# Top.net
KiCad netlist of a schematic drawn in Altium Designer
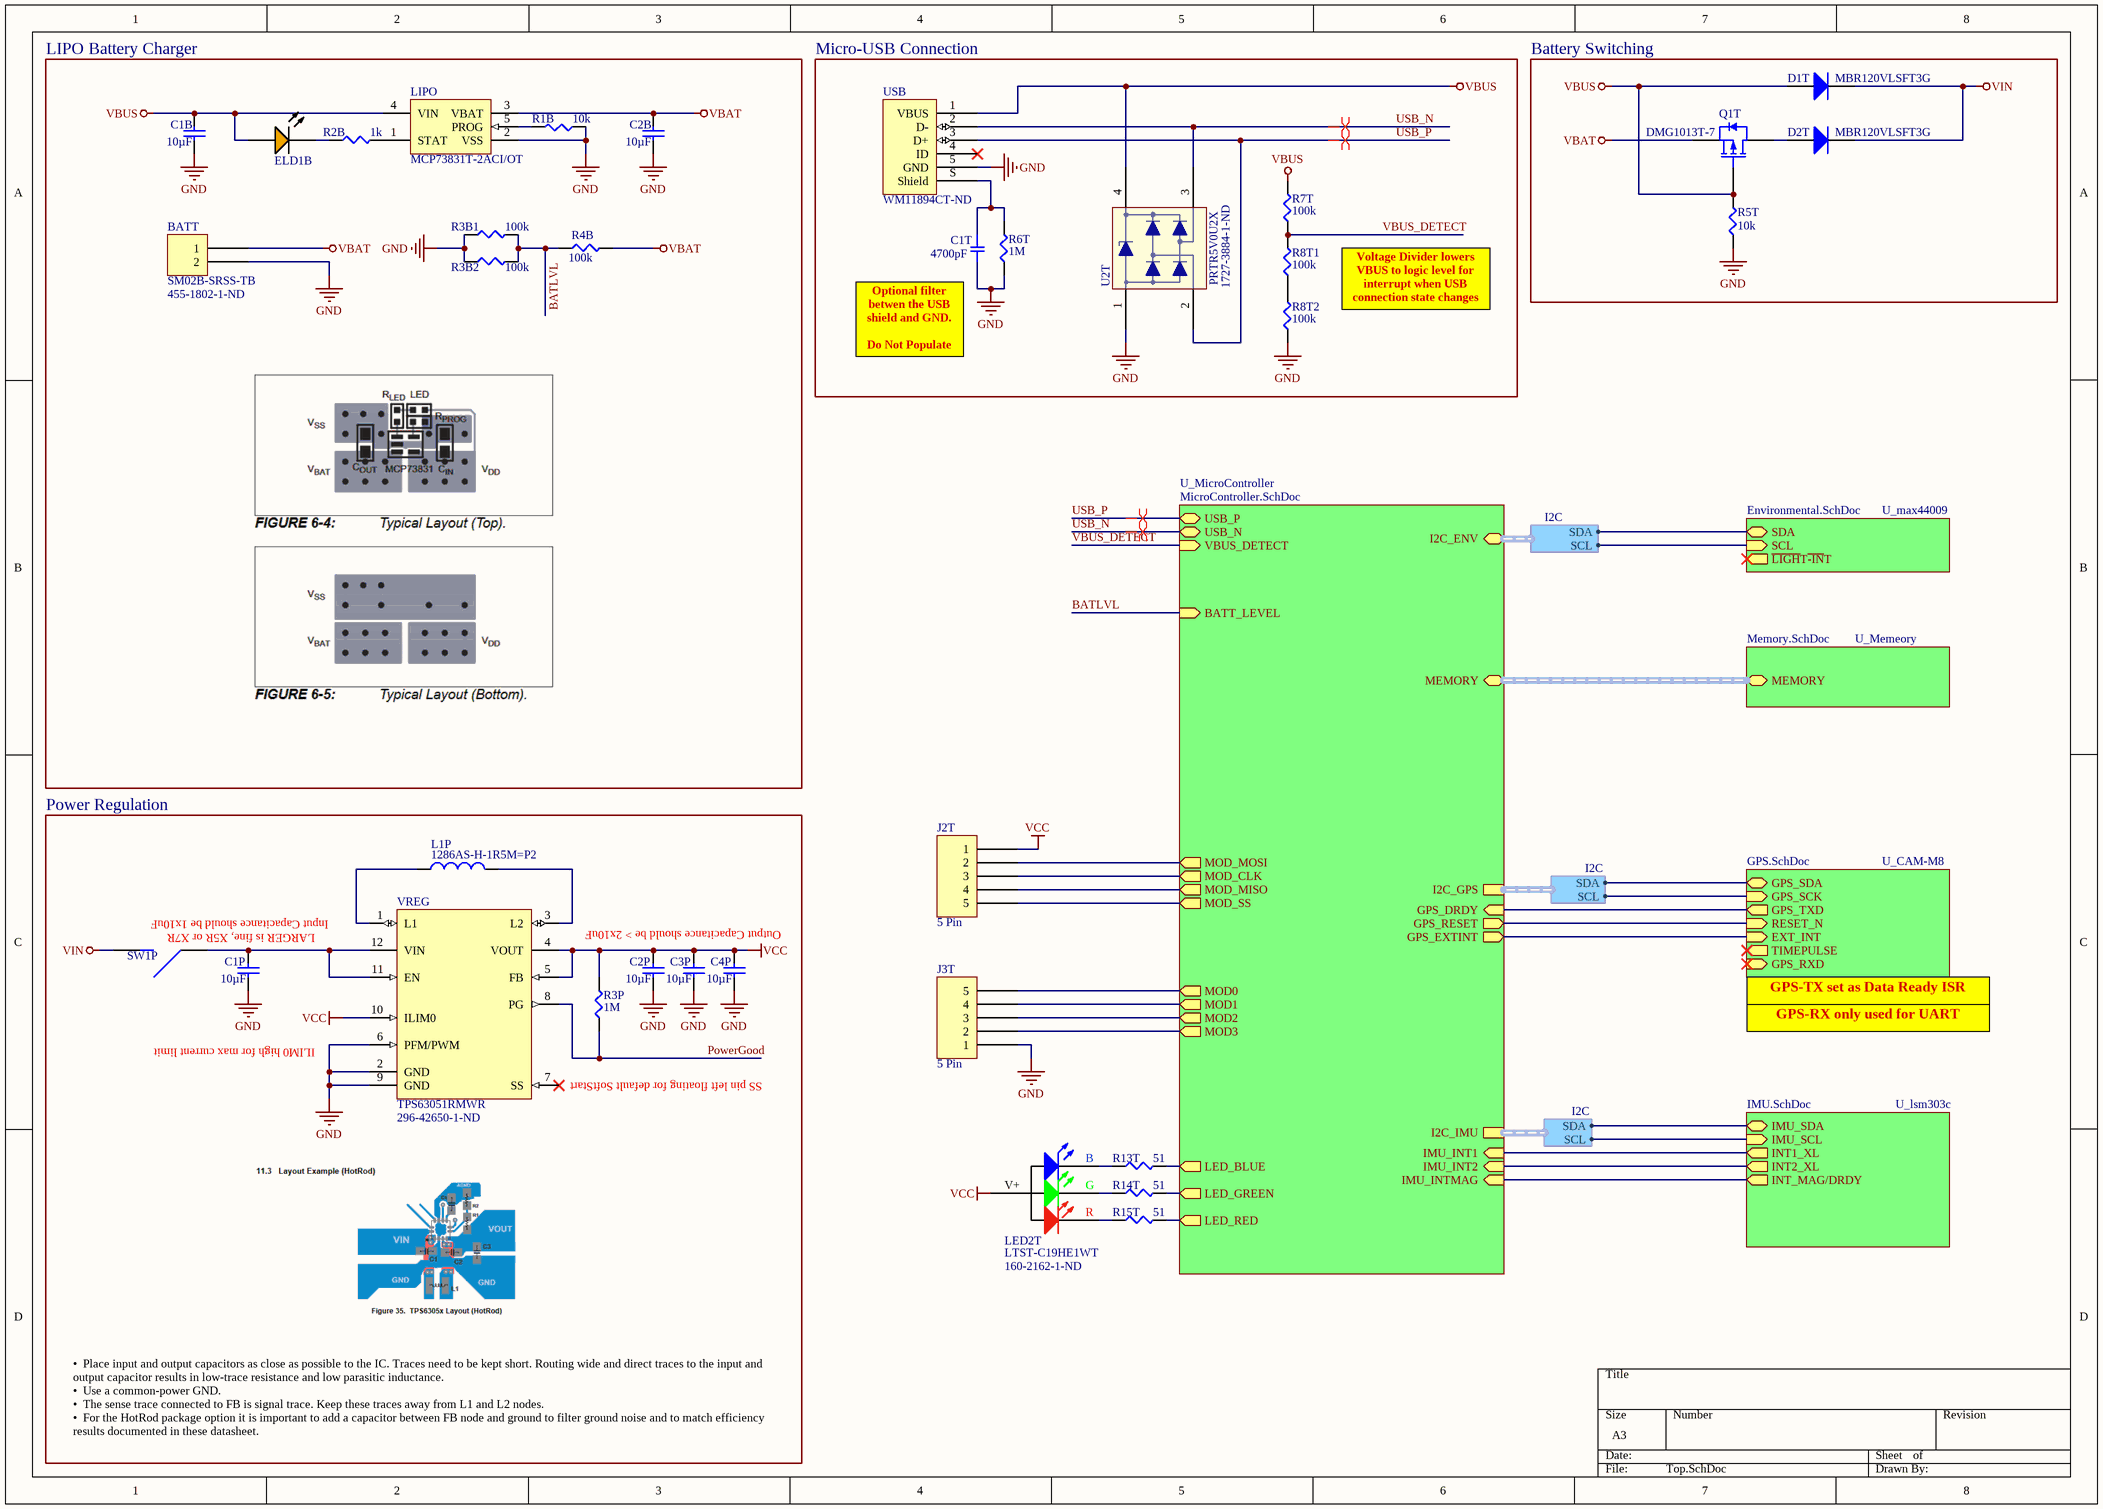
[diagram p0: Top.SchDoc]

(export (version "E")
  (design (tool "Eeschema 10.0.6"))
  (components
    (comp (ref "BATT")
      (value "SM02B-SRSS-TB")
      (footprint "JST S2B-PH-SM4")
      (fields (field (name "SUPPLIER PART NUMBER 1") "455-1802-1-ND"))
      (libsource (lib "Connectors") (part "2 Pin"))
    )
    (comp (ref "C1B")
      (value "GRT188R61C106KE13D")
      (footprint "C0603N")
      (description "10µF 16V Ceramic Capacitor X5R 0603")
      (fields
        (field (name "HOUSEPART") "NO")
        (field (name "TOLERANCE") "±10%")
        (field (name "CAPACITANCE") "10µF")
      )
      (libsource (lib "MF_Passives") (part "CAPACITOR_NP"))
    )
    (comp (ref "C1P")
      (value "GRT188R61C106KE13D")
      (footprint "C0603N")
      (description "10µF 16V Ceramic Capacitor X5R 0603")
      (fields
        (field (name "HOUSEPART") "NO")
        (field (name "TOLERANCE") "±10%")
        (field (name "CAPACITANCE") "10µF")
      )
      (libsource (lib "MF_Passives") (part "CAPACITOR_NP"))
    )
    (comp (ref "C1T")
      (value "4700pF")
      (footprint "C0603N")
      (description "CAP CER 4700PF 100V X7R 0603")
      (fields
        (field (name "DIGI-KEY PART NUMBER") "490-4930-1-ND")
        (field (name "PART NUMBER") "GCM188R72A472KA37D")
      )
      (libsource (lib "capacitor_murata_0603") (part "GCM188R72A472KA37D"))
    )
    (comp (ref "C2B")
      (value "GRT188R61C106KE13D")
      (footprint "C0603N")
      (description "10µF 16V Ceramic Capacitor X5R 0603")
      (fields
        (field (name "HOUSEPART") "NO")
        (field (name "TOLERANCE") "±10%")
        (field (name "CAPACITANCE") "10µF")
      )
      (libsource (lib "MF_Passives") (part "CAPACITOR_NP"))
    )
    (comp (ref "C2P")
      (value "GRT188R61C106KE13D")
      (footprint "C0603N")
      (description "10µF 16V Ceramic Capacitor X5R 0603")
      (fields
        (field (name "HOUSEPART") "NO")
        (field (name "TOLERANCE") "±10%")
        (field (name "CAPACITANCE") "10µF")
      )
      (libsource (lib "MF_Passives") (part "CAPACITOR_NP"))
    )
    (comp (ref "C3P")
      (value "GRT188R61C106KE13D")
      (footprint "C0603N")
      (description "10µF 16V Ceramic Capacitor X5R 0603")
      (fields
        (field (name "HOUSEPART") "NO")
        (field (name "TOLERANCE") "±10%")
        (field (name "CAPACITANCE") "10µF")
      )
      (libsource (lib "MF_Passives") (part "CAPACITOR_NP"))
    )
    (comp (ref "C4P")
      (value "GRT188R61C106KE13D")
      (footprint "C0603N")
      (description "10µF 16V Ceramic Capacitor X5R 0603")
      (fields
        (field (name "HOUSEPART") "NO")
        (field (name "TOLERANCE") "±10%")
        (field (name "CAPACITANCE") "10µF")
      )
      (libsource (lib "MF_Passives") (part "CAPACITOR_NP"))
    )
    (comp (ref "D1T")
      (value "MBR120VLSFT3G")
      (footprint "MBR120VLSFT3G")
      (description "Diode Schottky 20V 1A Surface Mount SOD-123FL")
      (libsource (lib "OnSemi") (part "MBR120VLSFT3G"))
    )
    (comp (ref "D2T")
      (value "MBR120VLSFT3G")
      (footprint "MBR120VLSFT3G")
      (description "Diode Schottky 20V 1A Surface Mount SOD-123FL")
      (libsource (lib "OnSemi") (part "MBR120VLSFT3G"))
    )
    (comp (ref "ELD1B")
      (value "LTST-C190KFKT")
      (footprint "LED_0603")
      (description "LED Uni-Color Orange, 75 mW, 30 mA")
      (libsource (lib "Lite-On") (part "CMP-1544850-3"))
    )
    (comp (ref "J2T") (value "5 Pin") (footprint "Pinhead_1x5") (libsource (lib "") (part "5 Pin_1")))
    (comp (ref "J3T") (value "5 Pin") (footprint "Pinhead_1x5") (libsource (lib "Connectors") (part "5 Pin")))
    (comp (ref "L1P")
      (value "1286AS-H-1R5M=P2")
      (footprint "L0806_N")
      (description "FIXED IND 1.5UH 2A 114 MOHM SMD")
      (libsource (lib "Passives") (part "INDUCTOR"))
    )
    (comp (ref "LED2T")
      (value "LTST-C19HE1WT")
      (footprint "LED_0606_160X160X35")
      (description "RGB LED 0606 (1616 metric)")
      (fields (field (name "SUPPLIER PART NUMBER 1") "160-2162-1-ND"))
      (libsource (lib "Lite-On") (part "LTST-C19HE1WT"))
    )
    (comp (ref "LIPO")
      (value "MCP73831T-2ACI/OT")
      (footprint "SOT-23-5_MC")
      (description "MCP73831 Series Single-Cell Li-Ion/Li-Polymer Battery Charge Controller SOT-23-5")
      (libsource (lib "Microchip") (part "MCHP-MCP73831T-5"))
    )
    (comp (ref "Q1T")
      (value "DMG1013T-7")
      (footprint "SOT50P175X90-3N")
      (description "P-Channel SOT-523")
      (libsource (lib "diodesInc") (part "DMG1013T-7c2930a883c7b1d54"))
    )
    (comp (ref "R1B")
      (value "10k")
      (footprint "SMD-0603-RES")
      (description "RES SMD 10K OHM 1% 1/10W 0603")
      (fields
        (field (name "PART NUMBER") "ERJ-3EKF1002V")
        (field (name "DIGI-KEY PART NUMBER") "P10.0KHCT-ND")
      )
      (libsource (lib "Panasonic_ERJ_0603") (part "ERJ-3EKF1002V"))
    )
    (comp (ref "R2B")
      (value "1k")
      (footprint "SMD-0603-RES")
      (description "RES SMD 1K OHM 1% 1/10W 0603")
      (fields
        (field (name "PART NUMBER") "ERJ-3EKF1001V")
        (field (name "DIGI-KEY PART NUMBER") "P1.00KHCT-ND")
      )
      (libsource (lib "Panasonic_ERJ_0603") (part "ERJ-3EKF1001V"))
    )
    (comp (ref "R3B1")
      (value "100k")
      (footprint "SMD-0603-RES")
      (description "RES SMD 100K OHM 1% 1/10W 0603")
      (fields
        (field (name "PART NUMBER") "ERJ-3EKF1003V")
        (field (name "DIGI-KEY PART NUMBER") "P100KHCT-ND")
      )
      (libsource (lib "Panasonic_ERJ_0603") (part "ERJ-3EKF1003V"))
    )
    (comp (ref "R3B2")
      (value "100k")
      (footprint "SMD-0603-RES")
      (description "RES SMD 100K OHM 1% 1/10W 0603")
      (fields
        (field (name "PART NUMBER") "ERJ-3EKF1003V")
        (field (name "DIGI-KEY PART NUMBER") "P100KHCT-ND")
      )
      (libsource (lib "Panasonic_ERJ_0603") (part "ERJ-3EKF1003V"))
    )
    (comp (ref "R3P")
      (value "1M")
      (footprint "SMD-0603-RES")
      (description "RES SMD 1M OHM 1% 1/10W 0603")
      (fields
        (field (name "PART NUMBER") "ERJ-3EKF1004V")
        (field (name "DIGI-KEY PART NUMBER") "P1.00MHCT-ND")
      )
      (libsource (lib "Panasonic_ERJ_0603") (part "ERJ-3EKF1004V"))
    )
    (comp (ref "R4B")
      (value "100k")
      (footprint "SMD-0603-RES")
      (description "RES SMD 100K OHM 1% 1/10W 0603")
      (fields
        (field (name "PART NUMBER") "ERJ-3EKF1003V")
        (field (name "DIGI-KEY PART NUMBER") "P100KHCT-ND")
      )
      (libsource (lib "Panasonic_ERJ_0603") (part "ERJ-3EKF1003V"))
    )
    (comp (ref "R5T")
      (value "10k")
      (footprint "SMD-0603-RES")
      (description "RES SMD 10K OHM 1% 1/10W 0603")
      (fields
        (field (name "PART NUMBER") "ERJ-3EKF1002V")
        (field (name "DIGI-KEY PART NUMBER") "P10.0KHCT-ND")
      )
      (libsource (lib "Panasonic_ERJ_0603") (part "ERJ-3EKF1002V"))
    )
    (comp (ref "R6T")
      (value "1M")
      (footprint "SMD-0603-RES")
      (description "RES SMD 1M OHM 1% 1/10W 0603")
      (fields
        (field (name "PART NUMBER") "ERJ-3EKF1004V")
        (field (name "DIGI-KEY PART NUMBER") "P1.00MHCT-ND")
      )
      (libsource (lib "Panasonic_ERJ_0603") (part "ERJ-3EKF1004V"))
    )
    (comp (ref "R7T")
      (value "100k")
      (footprint "SMD-0603-RES")
      (description "RES SMD 100K OHM 1% 1/10W 0603")
      (fields
        (field (name "PART NUMBER") "ERJ-3EKF1003V")
        (field (name "DIGI-KEY PART NUMBER") "P100KHCT-ND")
      )
      (libsource (lib "Panasonic_ERJ_0603") (part "ERJ-3EKF1003V"))
    )
    (comp (ref "R8T1")
      (value "100k")
      (footprint "SMD-0603-RES")
      (description "RES SMD 100K OHM 1% 1/10W 0603")
      (fields
        (field (name "PART NUMBER") "ERJ-3EKF1003V")
        (field (name "DIGI-KEY PART NUMBER") "P100KHCT-ND")
      )
      (libsource (lib "Panasonic_ERJ_0603") (part "ERJ-3EKF1003V"))
    )
    (comp (ref "R8T2")
      (value "100k")
      (footprint "SMD-0603-RES")
      (description "RES SMD 100K OHM 1% 1/10W 0603")
      (fields
        (field (name "PART NUMBER") "ERJ-3EKF1003V")
        (field (name "DIGI-KEY PART NUMBER") "P100KHCT-ND")
      )
      (libsource (lib "Panasonic_ERJ_0603") (part "ERJ-3EKF1003V"))
    )
    (comp (ref "R13T")
      (value "51")
      (footprint "SMD-0603-RES")
      (description "RES SMD 51 OHM 1% 1/10W 0603")
      (fields
        (field (name "PART NUMBER") "ERJ-3EKF51R0V")
        (field (name "DIGI-KEY PART NUMBER") "P51.0HCT-ND")
      )
      (libsource (lib "Panasonic_ERJ_0603") (part "ERJ-3EKF51R0V"))
    )
    (comp (ref "R14T")
      (value "51")
      (footprint "SMD-0603-RES")
      (description "RES SMD 51 OHM 1% 1/10W 0603")
      (fields
        (field (name "PART NUMBER") "ERJ-3EKF51R0V")
        (field (name "DIGI-KEY PART NUMBER") "P51.0HCT-ND")
      )
      (libsource (lib "Panasonic_ERJ_0603") (part "ERJ-3EKF51R0V"))
    )
    (comp (ref "R15T")
      (value "51")
      (footprint "SMD-0603-RES")
      (description "RES SMD 51 OHM 1% 1/10W 0603")
      (fields
        (field (name "PART NUMBER") "ERJ-3EKF51R0V")
        (field (name "DIGI-KEY PART NUMBER") "P51.0HCT-ND")
      )
      (libsource (lib "Panasonic_ERJ_0603") (part "ERJ-3EKF51R0V"))
    )
    (comp (ref "SW1P")
      (value "SPST")
      (footprint "Pinhead254_90_1x2")
      (description "SPST Switch")
      (libsource (lib "mechanical") (part "SPST switch"))
    )
    (comp (ref "U2T")
      (value "PRTR5V0U2X")
      (footprint "SOT143B")
      (fields (field (name "SUPPLIER PART NUMBER 1") "1727-3884-1-ND"))
      (libsource (lib "PRTR5V0U2X") (part "PRTR5V0U2X"))
    )
    (comp (ref "USB")
      (value "WM11894CT-ND")
      (footprint "MOLEX_105443-1101")
      (libsource (lib "Connectors") (part "USB 2.0 Type B Micro"))
    )
    (comp (ref "VREG")
      (value "TPS63051RMWR")
      (footprint "QFN12P50_250X250X100")
      (description "Single Inductor Buck Boost Converter 12-VQFN")
      (fields
        (field (name "MANUFACTURER") "Texas Instruments")
        (field (name "SUPPLIER PART NUMBER 1") "296-42650-1-ND")
      )
      (libsource (lib "TI") (part "TPS63051RMWR"))
    )
  )
  (nets
    (net (code "2") (name "/BATLVL") (class "Default")
      (node (ref "R3B1") (pin "2") (pinfunction "2_2") (pintype "passive"))
      (node (ref "R3B2") (pin "2") (pinfunction "2_2") (pintype "passive"))
      (node (ref "R4B") (pin "1") (pinfunction "1_1") (pintype "passive"))
    )
    (net (code "14") (name "/LED_BLUE") (class "Default")
      (node (ref "R13T") (pin "2") (pinfunction "2_2") (pintype "passive"))
    )
    (net (code "15") (name "/LED_GREEN") (class "Default")
      (node (ref "R14T") (pin "2") (pinfunction "2_2") (pintype "passive"))
    )
    (net (code "16") (name "/LED_RED") (class "Default")
      (node (ref "R15T") (pin "2") (pinfunction "2_2") (pintype "passive"))
    )
    (net (code "18") (name "/MOD0") (class "Default")
      (node (ref "J3T") (pin "5") (pinfunction "5_5") (pintype "passive"))
    )
    (net (code "19") (name "/MOD1") (class "Default")
      (node (ref "J3T") (pin "4") (pinfunction "4_4") (pintype "passive"))
    )
    (net (code "20") (name "/MOD2") (class "Default")
      (node (ref "J3T") (pin "3") (pinfunction "3_3") (pintype "passive"))
    )
    (net (code "21") (name "/MOD3") (class "Default")
      (node (ref "J3T") (pin "2") (pinfunction "2_2") (pintype "passive"))
    )
    (net (code "22") (name "/MOD_CLK") (class "Default")
      (node (ref "J2T") (pin "3") (pinfunction "3_3") (pintype "passive"))
    )
    (net (code "23") (name "/MOD_MISO") (class "Default")
      (node (ref "J2T") (pin "4") (pinfunction "4_4") (pintype "passive"))
    )
    (net (code "24") (name "/MOD_MOSI") (class "Default")
      (node (ref "J2T") (pin "2") (pinfunction "2_2") (pintype "passive"))
    )
    (net (code "25") (name "/MOD_SS") (class "Default")
      (node (ref "J2T") (pin "5") (pinfunction "5_5") (pintype "passive"))
    )
    (net (code "26") (name "/PowerGood") (class "Default")
      (node (ref "R3P") (pin "1") (pinfunction "1_1") (pintype "passive"))
      (node (ref "VREG") (pin "8") (pinfunction "PG_8") (pintype "output"))
    )
    (net (code "30") (name "/USB_N") (class "Default")
      (node (ref "U2T") (pin "3") (pinfunction "I/O2_3") (pintype "passive"))
      (node (ref "USB") (pin "2") (pinfunction "D-_2") (pintype "bidirectional"))
    )
    (net (code "31") (name "/USB_P") (class "Default")
      (node (ref "U2T") (pin "2") (pinfunction "I/O1_2") (pintype "passive"))
      (node (ref "USB") (pin "3") (pinfunction "D+_3") (pintype "bidirectional"))
    )
    (net (code "32") (name "/VBUS_DETECT") (class "Default")
      (node (ref "R7T") (pin "1") (pinfunction "1_1") (pintype "passive"))
      (node (ref "R8T1") (pin "2") (pinfunction "2_2") (pintype "passive"))
    )
    (net (code "35") (name "GND") (class "Default")
      (node (ref "BATT") (pin "2") (pinfunction "2_2") (pintype "passive"))
      (node (ref "C1B") (pin "1") (pinfunction "1_1") (pintype "passive"))
      (node (ref "C1P") (pin "1") (pinfunction "1_1") (pintype "passive"))
      (node (ref "C1T") (pin "2") (pinfunction "2_2") (pintype "passive"))
      (node (ref "C2B") (pin "1") (pinfunction "1_1") (pintype "passive"))
      (node (ref "C2P") (pin "1") (pinfunction "1_1") (pintype "passive"))
      (node (ref "C3P") (pin "1") (pinfunction "1_1") (pintype "passive"))
      (node (ref "C4P") (pin "1") (pinfunction "1_1") (pintype "passive"))
      (node (ref "J3T") (pin "1") (pinfunction "1_1") (pintype "passive"))
      (node (ref "LIPO") (pin "2") (pinfunction "VSS_2") (pintype "power_in"))
      (node (ref "R1B") (pin "1") (pinfunction "1_1") (pintype "passive"))
      (node (ref "R3B1") (pin "1") (pinfunction "1_1") (pintype "passive"))
      (node (ref "R3B2") (pin "1") (pinfunction "1_1") (pintype "passive"))
      (node (ref "R5T") (pin "1") (pinfunction "1_1") (pintype "passive"))
      (node (ref "R6T") (pin "1") (pinfunction "1_1") (pintype "passive"))
      (node (ref "R8T2") (pin "1") (pinfunction "1_1") (pintype "passive"))
      (node (ref "U2T") (pin "1") (pinfunction "GND_1") (pintype "passive"))
      (node (ref "USB") (pin "5") (pinfunction "GND_5") (pintype "power_in"))
      (node (ref "VREG") (pin "2") (pinfunction "GND_2") (pintype "power_in"))
      (node (ref "VREG") (pin "6") (pinfunction "PFM/PWM_6") (pintype "input"))
      (node (ref "VREG") (pin "9") (pinfunction "GND_9") (pintype "power_in"))
    )
    (net (code "36") (name "Net-(D2T-A)") (class "Default")
      (node (ref "D2T") (pin "1") (pinfunction "A_1") (pintype "passive"))
      (node (ref "Q1T") (pin "3") (pinfunction "D_3") (pintype "passive"))
    )
    (net (code "37") (name "Net-(ELD1B-K)") (class "Default")
      (node (ref "ELD1B") (pin "2") (pinfunction "K_2") (pintype "passive"))
      (node (ref "R2B") (pin "1") (pinfunction "1_1") (pintype "passive"))
    )
    (net (code "38") (name "Net-(LED2T-B)") (class "Default")
      (node (ref "LED2T") (pin "3") (pinfunction "B_3") (pintype "passive"))
      (node (ref "R13T") (pin "1") (pinfunction "1_1") (pintype "passive"))
    )
    (net (code "39") (name "Net-(LED2T-G)") (class "Default")
      (node (ref "LED2T") (pin "2") (pinfunction "G_2") (pintype "passive"))
      (node (ref "R14T") (pin "1") (pinfunction "1_1") (pintype "passive"))
    )
    (net (code "40") (name "Net-(LED2T-R)") (class "Default")
      (node (ref "LED2T") (pin "1") (pinfunction "R_1") (pintype "passive"))
      (node (ref "R15T") (pin "1") (pinfunction "1_1") (pintype "passive"))
    )
    (net (code "41") (name "Net-(LIPO-PROG)") (class "Default")
      (node (ref "LIPO") (pin "5") (pinfunction "PROG_5") (pintype "input"))
      (node (ref "R1B") (pin "2") (pinfunction "2_2") (pintype "passive"))
    )
    (net (code "42") (name "Net-(LIPO-STAT)") (class "Default")
      (node (ref "LIPO") (pin "1") (pinfunction "STAT_1") (pintype "tri_state"))
      (node (ref "R2B") (pin "2") (pinfunction "2_2") (pintype "passive"))
    )
    (net (code "43") (name "Net-(R8T1-Pad1)") (class "Default")
      (node (ref "R8T1") (pin "1") (pinfunction "1_1") (pintype "passive"))
      (node (ref "R8T2") (pin "2") (pinfunction "2_2") (pintype "passive"))
    )
    (net (code "44") (name "Net-(USB-Shield)") (class "Default")
      (node (ref "C1T") (pin "1") (pinfunction "1_1") (pintype "passive"))
      (node (ref "R6T") (pin "2") (pinfunction "2_2") (pintype "passive"))
      (node (ref "USB") (pin "S") (pinfunction "Shield_S") (pintype "passive"))
    )
    (net (code "45") (name "Net-(VREG-EN)") (class "Default")
      (node (ref "C1P") (pin "2") (pinfunction "2_2") (pintype "passive"))
      (node (ref "SW1P") (pin "1") (pinfunction "1_1") (pintype "passive"))
      (node (ref "VREG") (pin "11") (pinfunction "EN_11") (pintype "input"))
      (node (ref "VREG") (pin "12") (pinfunction "VIN_12") (pintype "power_in"))
    )
    (net (code "46") (name "Net-(VREG-L1)") (class "Default")
      (node (ref "L1P") (pin "1") (pinfunction "1_1") (pintype "passive"))
      (node (ref "VREG") (pin "1") (pinfunction "L1_1") (pintype "bidirectional"))
    )
    (net (code "47") (name "Net-(VREG-L2)") (class "Default")
      (node (ref "L1P") (pin "2") (pinfunction "2_2") (pintype "passive"))
      (node (ref "VREG") (pin "3") (pinfunction "L2_3") (pintype "bidirectional"))
    )
    (net (code "48") (name "VBAT") (class "Default")
      (node (ref "BATT") (pin "1") (pinfunction "1_1") (pintype "passive"))
      (node (ref "C2B") (pin "2") (pinfunction "2_2") (pintype "passive"))
      (node (ref "LIPO") (pin "3") (pinfunction "VBAT_3") (pintype "power_in"))
      (node (ref "Q1T") (pin "2") (pinfunction "S_2") (pintype "passive"))
      (node (ref "R4B") (pin "2") (pinfunction "2_2") (pintype "passive"))
    )
    (net (code "49") (name "VBUS") (class "Default")
      (node (ref "C1B") (pin "2") (pinfunction "2_2") (pintype "passive"))
      (node (ref "D1T") (pin "1") (pinfunction "A_1") (pintype "passive"))
      (node (ref "ELD1B") (pin "1") (pinfunction "A_1") (pintype "passive"))
      (node (ref "LIPO") (pin "4") (pinfunction "VIN_4") (pintype "power_in"))
      (node (ref "Q1T") (pin "1") (pinfunction "G_1") (pintype "passive"))
      (node (ref "R5T") (pin "2") (pinfunction "2_2") (pintype "passive"))
      (node (ref "R7T") (pin "2") (pinfunction "2_2") (pintype "passive"))
      (node (ref "U2T") (pin "4") (pinfunction "VCC_4") (pintype "passive"))
      (node (ref "USB") (pin "1") (pinfunction "VBUS_1") (pintype "power_in"))
    )
    (net (code "50") (name "VCC") (class "Default")
      (node (ref "C2P") (pin "2") (pinfunction "2_2") (pintype "passive"))
      (node (ref "C3P") (pin "2") (pinfunction "2_2") (pintype "passive"))
      (node (ref "C4P") (pin "2") (pinfunction "2_2") (pintype "passive"))
      (node (ref "J2T") (pin "1") (pinfunction "1_1") (pintype "passive"))
      (node (ref "LED2T") (pin "4") (pinfunction "A_4") (pintype "passive"))
      (node (ref "R3P") (pin "2") (pinfunction "2_2") (pintype "passive"))
      (node (ref "VREG") (pin "10") (pinfunction "ILIM0_10") (pintype "input"))
      (node (ref "VREG") (pin "4") (pinfunction "VOUT_4") (pintype "power_in"))
      (node (ref "VREG") (pin "5") (pinfunction "FB_5") (pintype "input"))
    )
    (net (code "51") (name "VIN") (class "Default")
      (node (ref "D1T") (pin "2") (pinfunction "K_2") (pintype "passive"))
      (node (ref "D2T") (pin "2") (pinfunction "K_2") (pintype "passive"))
      (node (ref "SW1P") (pin "2") (pinfunction "2_2") (pintype "passive"))
    )
    (net (code "52") (name "unconnected-(USB-ID-Pad4)") (class "Default")
      (node (ref "USB") (pin "4") (pinfunction "ID_4") (pintype "passive+no_connect"))
    )
    (net (code "53") (name "unconnected-(VREG-SS-Pad7)") (class "Default")
      (node (ref "VREG") (pin "7") (pinfunction "SS_7") (pintype "input+no_connect"))
    )
  )
)
